# Sheet1_SchDoc_lab2.net
KiCad netlist of a schematic drawn in Altium Designer
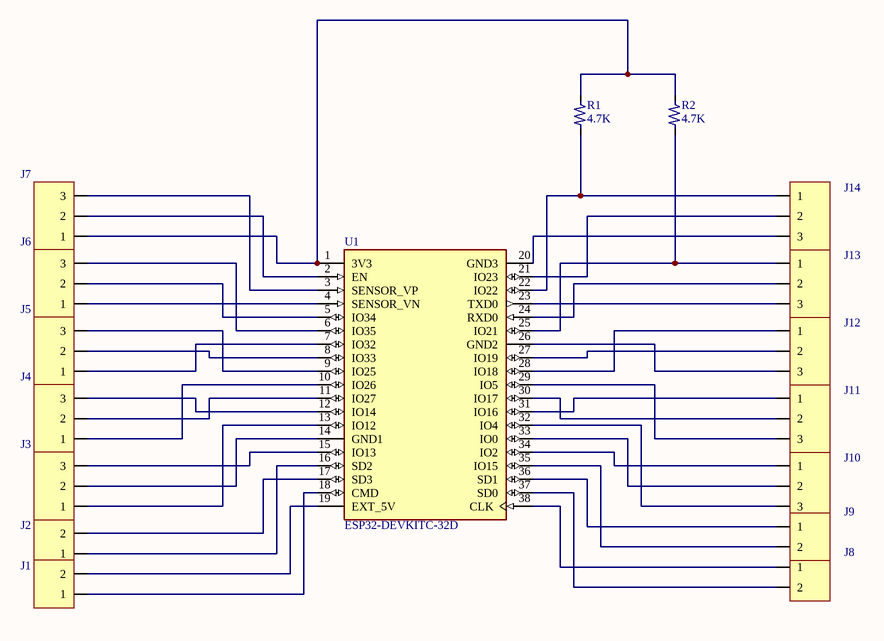
[diagram p0: Sheet1.SchDoc lab2.SchDoc]

(export (version "E")
  (design (tool "Eeschema 10.0.6"))
  (components
    (comp (ref "J1") (value "~") (footprint "TB_200Mil 2 P") (libsource (lib "") (part "TB 2 PIN_1")))
    (comp (ref "J2") (value "~") (footprint "TB_200Mil 2 P") (libsource (lib "") (part "TB 2 PIN_1")))
    (comp (ref "J3")
      (value "~")
      (footprint "TB_200Mil 3 P")
      (libsource (lib "Library Connector") (part "TB 3 PIN"))
    )
    (comp (ref "J4")
      (value "~")
      (footprint "TB_200Mil 3 P")
      (libsource (lib "Library Connector") (part "TB 3 PIN"))
    )
    (comp (ref "J5")
      (value "~")
      (footprint "TB_200Mil 3 P")
      (libsource (lib "Library Connector") (part "TB 3 PIN"))
    )
    (comp (ref "J6")
      (value "~")
      (footprint "TB_200Mil 3 P")
      (libsource (lib "Library Connector") (part "TB 3 PIN"))
    )
    (comp (ref "J7")
      (value "~")
      (footprint "TB_200Mil 3 P")
      (libsource (lib "Library Connector") (part "TB 3 PIN"))
    )
    (comp (ref "J8")
      (value "~")
      (footprint "TB_200Mil 2 P")
      (libsource (lib "Library Connector") (part "TB 2 PIN"))
    )
    (comp (ref "J9")
      (value "~")
      (footprint "TB_200Mil 2 P")
      (libsource (lib "Library Connector") (part "TB 2 PIN"))
    )
    (comp (ref "J10") (value "~") (footprint "TB_200Mil 3 P") (libsource (lib "") (part "TB 3 PIN_1")))
    (comp (ref "J11") (value "~") (footprint "TB_200Mil 3 P") (libsource (lib "") (part "TB 3 PIN_1")))
    (comp (ref "J12") (value "~") (footprint "TB_200Mil 3 P") (libsource (lib "") (part "TB 3 PIN_1")))
    (comp (ref "J13") (value "~") (footprint "TB_200Mil 3 P") (libsource (lib "") (part "TB 3 PIN_1")))
    (comp (ref "J14") (value "~") (footprint "TB_200Mil 3 P") (libsource (lib "") (part "TB 3 PIN_1")))
    (comp (ref "R1") (value "4.7K") (footprint "4.7K") (libsource (lib "Library 0.25w 1_") (part "4.7K")))
    (comp (ref "R2") (value "4.7K") (footprint "4.7K") (libsource (lib "Library 0.25w 1_") (part "4.7K")))
    (comp (ref "U1")
      (value "ESP32-DEVKITC-32D")
      (footprint "MODULE_ESP32-DEVKITC-32D")
      (description "EVAL BOARD FOR ESP-WROOM-32")
      (fields (field (name "MF") "Espressif Systems"))
      (libsource (lib "ESP32-DEVKITC-32D") (part "ESP32-DEVKITC-32D"))
    )
  )
  (nets
    (net (code "1") (name "Net-(U1-3V3)") (class "Default")
      (node (ref "J7") (pin "1") (pinfunction "1_1") (pintype "passive"))
      (node (ref "R1") (pin "2") (pintype "passive"))
      (node (ref "R2") (pin "2") (pintype "passive"))
      (node (ref "U1") (pin "1") (pinfunction "3V3_1") (pintype "power_in"))
    )
    (net (code "2") (name "Net-(U1-CLK)") (class "Default")
      (node (ref "J8") (pin "1") (pinfunction "1_1") (pintype "passive"))
      (node (ref "U1") (pin "38") (pinfunction "CLK_38") (pintype "input"))
    )
    (net (code "3") (name "Net-(U1-CMD)") (class "Default")
      (node (ref "J1") (pin "1") (pinfunction "1_1") (pintype "passive"))
      (node (ref "U1") (pin "18") (pinfunction "CMD_18") (pintype "bidirectional"))
    )
    (net (code "4") (name "Net-(U1-EN)") (class "Default")
      (node (ref "J7") (pin "2") (pinfunction "2_2") (pintype "passive"))
      (node (ref "U1") (pin "2") (pinfunction "EN_2") (pintype "input"))
    )
    (net (code "5") (name "Net-(U1-EXT_5V)") (class "Default")
      (node (ref "J1") (pin "2") (pinfunction "2_2") (pintype "passive"))
      (node (ref "U1") (pin "19") (pinfunction "EXT_5V_19") (pintype "power_in"))
    )
    (net (code "6") (name "Net-(U1-GND1)") (class "Default")
      (node (ref "J3") (pin "2") (pinfunction "2_2") (pintype "passive"))
      (node (ref "U1") (pin "14") (pinfunction "GND1_14") (pintype "power_in"))
    )
    (net (code "7") (name "Net-(U1-GND2)") (class "Default")
      (node (ref "J12") (pin "3") (pinfunction "3_3") (pintype "passive"))
      (node (ref "U1") (pin "26") (pinfunction "GND2_26") (pintype "power_in"))
    )
    (net (code "8") (name "Net-(U1-GND3)") (class "Default")
      (node (ref "J14") (pin "3") (pinfunction "3_3") (pintype "passive"))
      (node (ref "U1") (pin "20") (pinfunction "GND3_20") (pintype "power_in"))
    )
    (net (code "9") (name "Net-(U1-IO0)") (class "Default")
      (node (ref "J10") (pin "2") (pinfunction "2_2") (pintype "passive"))
      (node (ref "U1") (pin "33") (pinfunction "IO0_33") (pintype "bidirectional"))
    )
    (net (code "10") (name "Net-(U1-IO2)") (class "Default")
      (node (ref "J10") (pin "1") (pinfunction "1_1") (pintype "passive"))
      (node (ref "U1") (pin "34") (pinfunction "IO2_34") (pintype "bidirectional"))
    )
    (net (code "11") (name "Net-(U1-IO4)") (class "Default")
      (node (ref "J10") (pin "3") (pinfunction "3_3") (pintype "passive"))
      (node (ref "U1") (pin "32") (pinfunction "IO4_32") (pintype "bidirectional"))
    )
    (net (code "12") (name "Net-(U1-IO5)") (class "Default")
      (node (ref "J11") (pin "3") (pinfunction "3_3") (pintype "passive"))
      (node (ref "U1") (pin "29") (pinfunction "IO5_29") (pintype "bidirectional"))
    )
    (net (code "13") (name "Net-(U1-IO12)") (class "Default")
      (node (ref "J3") (pin "1") (pinfunction "1_1") (pintype "passive"))
      (node (ref "U1") (pin "13") (pinfunction "IO12_13") (pintype "bidirectional"))
    )
    (net (code "14") (name "Net-(U1-IO13)") (class "Default")
      (node (ref "J3") (pin "3") (pinfunction "3_3") (pintype "passive"))
      (node (ref "U1") (pin "15") (pinfunction "IO13_15") (pintype "bidirectional"))
    )
    (net (code "15") (name "Net-(U1-IO14)") (class "Default")
      (node (ref "J4") (pin "3") (pinfunction "3_3") (pintype "passive"))
      (node (ref "U1") (pin "12") (pinfunction "IO14_12") (pintype "bidirectional"))
    )
    (net (code "16") (name "Net-(U1-IO15)") (class "Default")
      (node (ref "J9") (pin "2") (pinfunction "2_2") (pintype "passive"))
      (node (ref "U1") (pin "35") (pinfunction "IO15_35") (pintype "bidirectional"))
    )
    (net (code "17") (name "Net-(U1-IO16)") (class "Default")
      (node (ref "J11") (pin "1") (pinfunction "1_1") (pintype "passive"))
      (node (ref "U1") (pin "31") (pinfunction "IO16_31") (pintype "bidirectional"))
    )
    (net (code "18") (name "Net-(U1-IO17)") (class "Default")
      (node (ref "J11") (pin "2") (pinfunction "2_2") (pintype "passive"))
      (node (ref "U1") (pin "30") (pinfunction "IO17_30") (pintype "bidirectional"))
    )
    (net (code "19") (name "Net-(U1-IO18)") (class "Default")
      (node (ref "J12") (pin "1") (pinfunction "1_1") (pintype "passive"))
      (node (ref "U1") (pin "28") (pinfunction "IO18_28") (pintype "bidirectional"))
    )
    (net (code "20") (name "Net-(U1-IO19)") (class "Default")
      (node (ref "J12") (pin "2") (pinfunction "2_2") (pintype "passive"))
      (node (ref "U1") (pin "27") (pinfunction "IO19_27") (pintype "bidirectional"))
    )
    (net (code "21") (name "Net-(U1-IO21)") (class "Default")
      (node (ref "J13") (pin "1") (pinfunction "1_1") (pintype "passive"))
      (node (ref "R2") (pin "1") (pintype "passive"))
      (node (ref "U1") (pin "25") (pinfunction "IO21_25") (pintype "bidirectional"))
    )
    (net (code "22") (name "Net-(U1-IO22)") (class "Default")
      (node (ref "J14") (pin "1") (pinfunction "1_1") (pintype "passive"))
      (node (ref "R1") (pin "1") (pintype "passive"))
      (node (ref "U1") (pin "22") (pinfunction "IO22_22") (pintype "bidirectional"))
    )
    (net (code "23") (name "Net-(U1-IO23)") (class "Default")
      (node (ref "J14") (pin "2") (pinfunction "2_2") (pintype "passive"))
      (node (ref "U1") (pin "21") (pinfunction "IO23_21") (pintype "bidirectional"))
    )
    (net (code "24") (name "Net-(U1-IO25)") (class "Default")
      (node (ref "J5") (pin "3") (pinfunction "3_3") (pintype "passive"))
      (node (ref "U1") (pin "9") (pinfunction "IO25_9") (pintype "bidirectional"))
    )
    (net (code "25") (name "Net-(U1-IO26)") (class "Default")
      (node (ref "J4") (pin "1") (pinfunction "1_1") (pintype "passive"))
      (node (ref "U1") (pin "10") (pinfunction "IO26_10") (pintype "bidirectional"))
    )
    (net (code "26") (name "Net-(U1-IO27)") (class "Default")
      (node (ref "J4") (pin "2") (pinfunction "2_2") (pintype "passive"))
      (node (ref "U1") (pin "11") (pinfunction "IO27_11") (pintype "bidirectional"))
    )
    (net (code "27") (name "Net-(U1-IO32)") (class "Default")
      (node (ref "J5") (pin "1") (pinfunction "1_1") (pintype "passive"))
      (node (ref "U1") (pin "7") (pinfunction "IO32_7") (pintype "bidirectional"))
    )
    (net (code "28") (name "Net-(U1-IO33)") (class "Default")
      (node (ref "J5") (pin "2") (pinfunction "2_2") (pintype "passive"))
      (node (ref "U1") (pin "8") (pinfunction "IO33_8") (pintype "bidirectional"))
    )
    (net (code "29") (name "Net-(U1-IO34)") (class "Default")
      (node (ref "J6") (pin "2") (pinfunction "2_2") (pintype "passive"))
      (node (ref "U1") (pin "5") (pinfunction "IO34_5") (pintype "bidirectional"))
    )
    (net (code "30") (name "Net-(U1-IO35)") (class "Default")
      (node (ref "J6") (pin "3") (pinfunction "3_3") (pintype "passive"))
      (node (ref "U1") (pin "6") (pinfunction "IO35_6") (pintype "bidirectional"))
    )
    (net (code "31") (name "Net-(U1-RXD0)") (class "Default")
      (node (ref "J13") (pin "2") (pinfunction "2_2") (pintype "passive"))
      (node (ref "U1") (pin "24") (pinfunction "RXD0_24") (pintype "input"))
    )
    (net (code "32") (name "Net-(U1-SD0)") (class "Default")
      (node (ref "J8") (pin "2") (pinfunction "2_2") (pintype "passive"))
      (node (ref "U1") (pin "37") (pinfunction "SD0_37") (pintype "bidirectional"))
    )
    (net (code "33") (name "Net-(U1-SD1)") (class "Default")
      (node (ref "J9") (pin "1") (pinfunction "1_1") (pintype "passive"))
      (node (ref "U1") (pin "36") (pinfunction "SD1_36") (pintype "bidirectional"))
    )
    (net (code "34") (name "Net-(U1-SD2)") (class "Default")
      (node (ref "J2") (pin "1") (pinfunction "1_1") (pintype "passive"))
      (node (ref "U1") (pin "16") (pinfunction "SD2_16") (pintype "bidirectional"))
    )
    (net (code "35") (name "Net-(U1-SD3)") (class "Default")
      (node (ref "J2") (pin "2") (pinfunction "2_2") (pintype "passive"))
      (node (ref "U1") (pin "17") (pinfunction "SD3_17") (pintype "bidirectional"))
    )
    (net (code "36") (name "Net-(U1-SENSOR_VN)") (class "Default")
      (node (ref "J6") (pin "1") (pinfunction "1_1") (pintype "passive"))
      (node (ref "U1") (pin "4") (pinfunction "SENSOR_VN_4") (pintype "input"))
    )
    (net (code "37") (name "Net-(U1-SENSOR_VP)") (class "Default")
      (node (ref "J7") (pin "3") (pinfunction "3_3") (pintype "passive"))
      (node (ref "U1") (pin "3") (pinfunction "SENSOR_VP_3") (pintype "input"))
    )
    (net (code "38") (name "Net-(U1-TXD0)") (class "Default")
      (node (ref "J13") (pin "3") (pinfunction "3_3") (pintype "passive"))
      (node (ref "U1") (pin "23") (pinfunction "TXD0_23") (pintype "output"))
    )
  )
)
